# AUDIO_MICROPHONE.net
KiCad netlist of a schematic drawn in Altium Designer
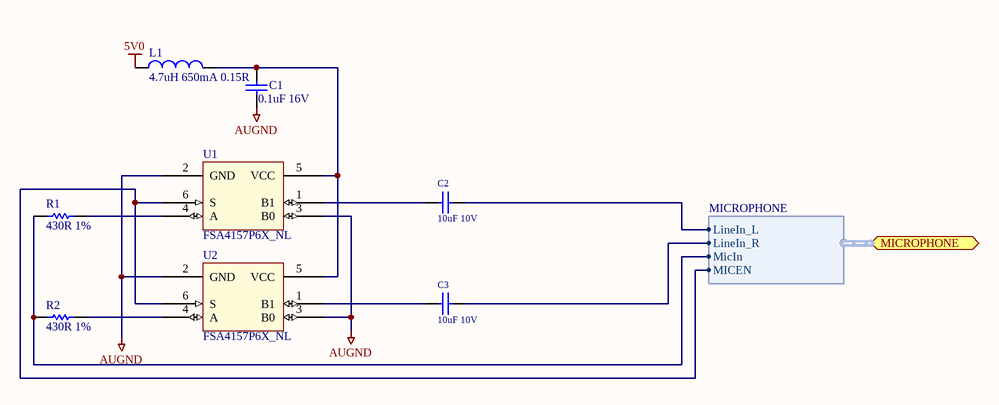
[diagram p0: AUDIO_MICROPHONE.SchDoc]

(export (version "E")
  (design (tool "Eeschema 10.0.6"))
  (components
    (comp (ref "C1")
      (value "0.1uF 16V")
      (footprint "CAPC1005-STAR")
      (description "Capacitor, Ceramic, 0.1uF 10% 16V 0402 (1005) X7R")
      (fields (field (name "TOLERANCE") "10 %"))
      (libsource (lib "AltiumDesignLibrary") (part "CAP-NP"))
    )
    (comp (ref "C2")
      (value "10uF 10V")
      (footprint "CAPC2012-STAR")
      (description "Capacitor, Ceramic, 10uF 10% 10V 0805 (2012) X5R")
      (fields (field (name "TOLERANCE") "10 %"))
      (libsource (lib "AltiumDesignLibrary") (part "CAP-NP"))
    )
    (comp (ref "C3")
      (value "10uF 10V")
      (footprint "CAPC2012-STAR")
      (description "Capacitor, Ceramic, 10uF 10% 10V 0805 (2012) X5R")
      (fields (field (name "TOLERANCE") "10 %"))
      (libsource (lib "AltiumDesignLibrary") (part "CAP-NP"))
    )
    (comp (ref "L1")
      (value "4.7uH 650mA 0.15R")
      (footprint "INDC3225")
      (description "Inductor, 4.7uH 650mA 0.15R 1210 (3225) LQH32CN4R7M11L")
      (libsource (lib "AltiumDesignLibrary") (part "IND"))
    )
    (comp (ref "R1")
      (value "430R 1%")
      (footprint "RESC1005-STAR")
      (description "Resistor, 430R 1% 0402 (1005)")
      (fields (field (name "TOLERANCE") "1 %"))
      (libsource (lib "AltiumDesignLibrary") (part "RES"))
    )
    (comp (ref "R2")
      (value "430R 1%")
      (footprint "RESC1005-STAR")
      (description "Resistor, 430R 1% 0402 (1005)")
      (fields (field (name "TOLERANCE") "1 %"))
      (libsource (lib "AltiumDesignLibrary") (part "RES"))
    )
    (comp (ref "U1")
      (value "FSA4157P6X_NL")
      (footprint "SC70_6L")
      (description "Low Voltage 1R  SPDT Analog Switch, SC70-6, 1.65-5.5v")
      (libsource (lib "AltiumDesignLibrary") (part "FSA4157"))
    )
    (comp (ref "U2")
      (value "FSA4157P6X_NL")
      (footprint "SC70_6L")
      (description "Low Voltage 1R  SPDT Analog Switch, SC70-6, 1.65-5.5v")
      (libsource (lib "AltiumDesignLibrary") (part "FSA4157"))
    )
  )
  (nets
    (net (code "2") (name "/LineIn_L") (class "Default")
      (node (ref "C2") (pin "2") (pinfunction "2_2") (pintype "passive"))
    )
    (net (code "3") (name "/LineIn_R") (class "Default")
      (node (ref "C3") (pin "2") (pinfunction "2_2") (pintype "passive"))
    )
    (net (code "4") (name "/MICEN") (class "Default")
      (node (ref "U1") (pin "6") (pinfunction "S_6") (pintype "input"))
      (node (ref "U2") (pin "6") (pinfunction "S_6") (pintype "input"))
    )
    (net (code "5") (name "/MicIn") (class "Default")
      (node (ref "R1") (pin "1") (pinfunction "1_1") (pintype "passive"))
      (node (ref "R2") (pin "1") (pinfunction "1_1") (pintype "passive"))
    )
    (net (code "7") (name "5V0") (class "Default")
      (node (ref "L1") (pin "2") (pinfunction "2_2") (pintype "passive"))
    )
    (net (code "8") (name "AUGND") (class "Default")
      (node (ref "C1") (pin "1") (pinfunction "1_1") (pintype "passive"))
      (node (ref "U1") (pin "2") (pinfunction "GND_2") (pintype "power_in"))
      (node (ref "U1") (pin "3") (pinfunction "B0_3") (pintype "bidirectional"))
      (node (ref "U2") (pin "2") (pinfunction "GND_2") (pintype "power_in"))
      (node (ref "U2") (pin "3") (pinfunction "B0_3") (pintype "bidirectional"))
    )
    (net (code "9") (name "Net-(U1-A)") (class "Default")
      (node (ref "R1") (pin "2") (pinfunction "2_2") (pintype "passive"))
      (node (ref "U1") (pin "4") (pinfunction "A_4") (pintype "bidirectional"))
    )
    (net (code "10") (name "Net-(U1-B1)") (class "Default")
      (node (ref "C2") (pin "1") (pinfunction "1_1") (pintype "passive"))
      (node (ref "U1") (pin "1") (pinfunction "B1_1") (pintype "bidirectional"))
    )
    (net (code "11") (name "Net-(U1-VCC)") (class "Default")
      (node (ref "C1") (pin "2") (pinfunction "2_2") (pintype "passive"))
      (node (ref "L1") (pin "1") (pinfunction "1_1") (pintype "passive"))
      (node (ref "U1") (pin "5") (pinfunction "VCC_5") (pintype "power_in"))
      (node (ref "U2") (pin "5") (pinfunction "VCC_5") (pintype "power_in"))
    )
    (net (code "12") (name "Net-(U2-A)") (class "Default")
      (node (ref "R2") (pin "2") (pinfunction "2_2") (pintype "passive"))
      (node (ref "U2") (pin "4") (pinfunction "A_4") (pintype "bidirectional"))
    )
    (net (code "13") (name "Net-(U2-B1)") (class "Default")
      (node (ref "C3") (pin "1") (pinfunction "1_1") (pintype "passive"))
      (node (ref "U2") (pin "1") (pinfunction "B1_1") (pintype "bidirectional"))
    )
  )
)
